# SEC_3002_HL_Power.net
KiCad netlist of a schematic drawn in Altium Designer
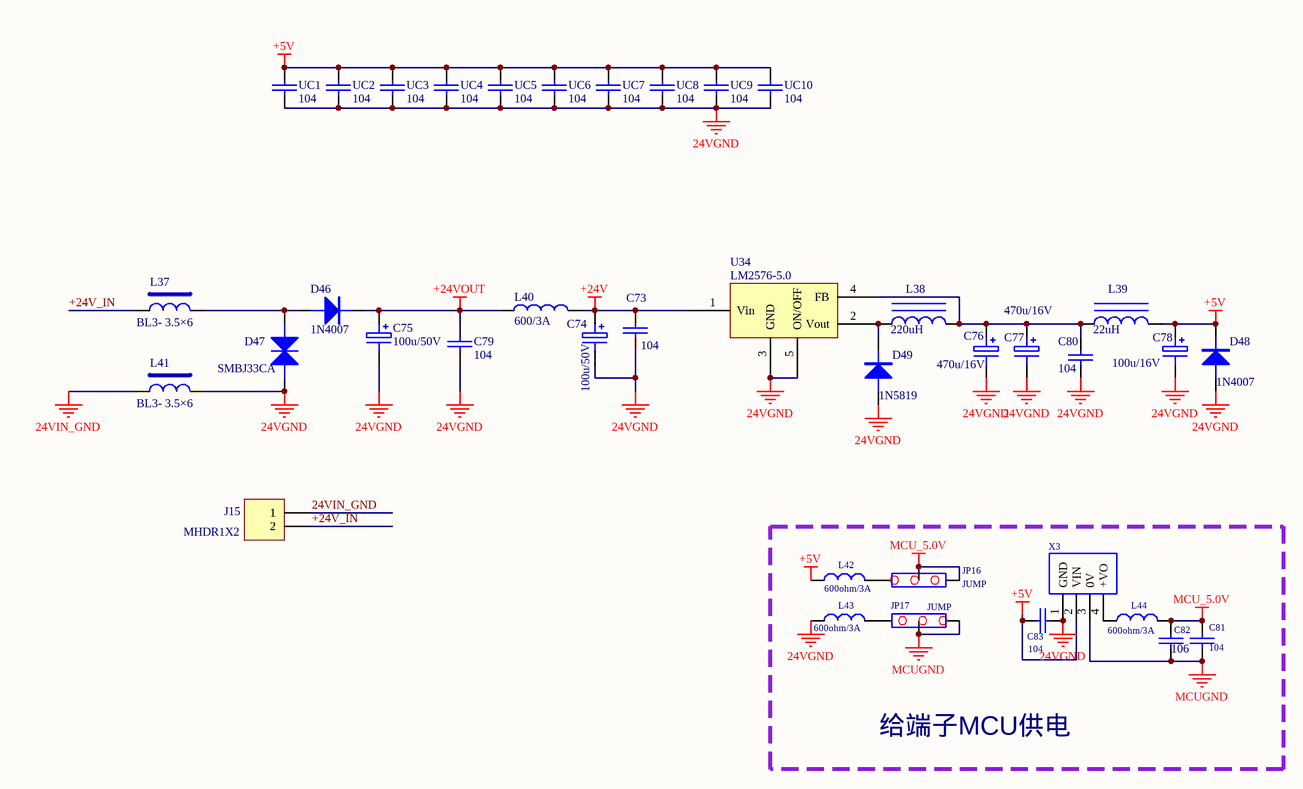
[diagram p0: SEC_3002_HL_Power.SchDoc]

(export (version "E")
  (design (tool "Eeschema 10.0.6"))
  (components
    (comp (ref "C73")
      (value "104")
      (footprint "C-0603")
      (description "Capacitor")
      (libsource (lib "*") (part "CAP"))
    )
    (comp (ref "C74")
      (value "100u/50V")
      (footprint "CAP-SMD-8*8*10")
      (description "Electrolytic Capacitor")
      (libsource (lib "*") (part "ELECTRO1"))
    )
    (comp (ref "C75")
      (value "100u/50V")
      (footprint "CAP-SMD-8*8*10")
      (description "Electrolytic Capacitor")
      (libsource (lib "*") (part "ELECTRO1"))
    )
    (comp (ref "C76")
      (value "470u/16V")
      (footprint "CAP-SMD-8*8*10")
      (description "Electrolytic Capacitor")
      (libsource (lib "*") (part "ELECTRO1"))
    )
    (comp (ref "C77")
      (value "470u/16V")
      (footprint "CAP-SMD-8*8*10")
      (description "Electrolytic Capacitor")
      (libsource (lib "*") (part "ELECTRO1"))
    )
    (comp (ref "C78")
      (value "100u/16V")
      (footprint "CAP-SMD-6.3")
      (description "Electrolytic Capacitor")
      (libsource (lib "*") (part "ELECTRO1"))
    )
    (comp (ref "C79")
      (value "104")
      (footprint "C-0603")
      (description "Capacitor")
      (libsource (lib "*") (part "CAP"))
    )
    (comp (ref "C80")
      (value "104")
      (footprint "C-0603")
      (description "Capacitor")
      (libsource (lib "*") (part "CAP"))
    )
    (comp (ref "C81")
      (value "104")
      (footprint "C-0603")
      (description "Capacitor")
      (libsource (lib "*") (part "CAP"))
    )
    (comp (ref "C82")
      (value "10V-106-±10%-[0805]")
      (footprint "C-0805")
      (description "Capacitor")
      (fields (field (name "ALTIUM_UNNAMED_1") "106"))
      (libsource (lib "*") (part "CAP"))
    )
    (comp (ref "C83")
      (value "104")
      (footprint "C-0603")
      (description "Capacitor")
      (libsource (lib "*") (part "CAP"))
    )
    (comp (ref "D46")
      (value "1N4007")
      (footprint "4526D")
      (description "Diode")
      (libsource (lib "*") (part "DIODE_A"))
    )
    (comp (ref "D47") (value "SMBJ33CA") (footprint "TVS-A") (libsource (lib "*") (part "TVS")))
    (comp (ref "D48")
      (value "1N4007")
      (footprint "4526D")
      (description "Diode")
      (libsource (lib "*") (part "DIODE_A"))
    )
    (comp (ref "D49")
      (value "1N5819")
      (footprint "4526D")
      (description "Diode")
      (libsource (lib "*") (part "DIODE_A"))
    )
    (comp (ref "J15")
      (value "MHDR1X2")
      (footprint "6.35MM-2PIN")
      (description "Header, 2-Pin")
      (fields (field (name "PUBLISHER") "Altium Limited"))
      (libsource (lib "Miscellaneous Connectors") (part "MHDR1X2"))
    )
    (comp (ref "JP16") (value "JUMP") (footprint "SIP3") (libsource (lib "*") (part "JUMP")))
    (comp (ref "JP17") (value "JUMP") (footprint "SIP3") (libsource (lib "*") (part "JUMP")))
    (comp (ref "L37")
      (value "BL3- 3.5×6")
      (footprint "L_C")
      (libsource (lib "JB-QBL-ST300_B_1") (part "INDUCTOR"))
    )
    (comp (ref "L38") (value "220uH") (footprint "L-7*7") (libsource (lib "*") (part "INDUCTOR IRON")))
    (comp (ref "L39") (value "22uH") (footprint "L-7*7") (libsource (lib "*") (part "INDUCTOR IRON")))
    (comp (ref "L40") (value "600/3A") (footprint "L-0805") (libsource (lib "*") (part "INDUCTOR1")))
    (comp (ref "L41")
      (value "BL3- 3.5×6")
      (footprint "L_C")
      (libsource (lib "JB-QBL-ST300_B_1") (part "INDUCTOR"))
    )
    (comp (ref "L42")
      (value "600ohm/3A")
      (footprint "L-0805")
      (description "60Ω-3A-[0805]")
      (fields (field (name "Comment") "BEAD"))
      (libsource (lib "*") (part "BEAD"))
    )
    (comp (ref "L43")
      (value "600ohm/3A")
      (footprint "L-0805")
      (description "60Ω-3A-[0805]")
      (fields (field (name "Comment") "BEAD"))
      (libsource (lib "*") (part "BEAD"))
    )
    (comp (ref "L44")
      (value "600ohm/3A")
      (footprint "L-0805")
      (description "60Ω-3A-[0805]")
      (fields (field (name "Comment") "BEAD"))
      (libsource (lib "*") (part "BEAD"))
    )
    (comp (ref "U34") (value "LM2576-5.0") (footprint "LM2576-5.0") (libsource (lib "*") (part "LM2576-5.0")))
    (comp (ref "UC1")
      (value "104")
      (footprint "C-0603")
      (description "Capacitor")
      (libsource (lib "*") (part "CAP"))
    )
    (comp (ref "UC2")
      (value "104")
      (footprint "C-0603")
      (description "Capacitor")
      (libsource (lib "*") (part "CAP"))
    )
    (comp (ref "UC3")
      (value "104")
      (footprint "C-0603")
      (description "Capacitor")
      (libsource (lib "*") (part "CAP"))
    )
    (comp (ref "UC4")
      (value "104")
      (footprint "C-0603")
      (description "Capacitor")
      (libsource (lib "*") (part "CAP"))
    )
    (comp (ref "UC5")
      (value "104")
      (footprint "C-0603")
      (description "Capacitor")
      (libsource (lib "*") (part "CAP"))
    )
    (comp (ref "UC6")
      (value "104")
      (footprint "C-0603")
      (description "Capacitor")
      (libsource (lib "*") (part "CAP"))
    )
    (comp (ref "UC7")
      (value "104")
      (footprint "C-0603")
      (description "Capacitor")
      (libsource (lib "*") (part "CAP"))
    )
    (comp (ref "UC8")
      (value "104")
      (footprint "C-0603")
      (description "Capacitor")
      (libsource (lib "*") (part "CAP"))
    )
    (comp (ref "UC9")
      (value "104")
      (footprint "C-0603")
      (description "Capacitor")
      (libsource (lib "*") (part "CAP"))
    )
    (comp (ref "UC10")
      (value "104")
      (footprint "C-0603")
      (description "Capacitor")
      (libsource (lib "*") (part "CAP"))
    )
    (comp (ref "X3")
      (value "B0505S-1WR2_")
      (footprint "B050S-1WR2")
      (description "B050S-1WR")
      (libsource (lib "*") (part "B0505S-1WR2_"))
    )
  )
  (nets
    (net (code "1") (name "+5V") (class "Default")
      (node (ref "C78") (pin "1") (pinfunction "1_1") (pintype "passive"))
      (node (ref "C83") (pin "1") (pinfunction "1_1") (pintype "passive"))
      (node (ref "D48") (pin "K") (pinfunction "K_K") (pintype "passive"))
      (node (ref "L39") (pin "1") (pinfunction "1_1") (pintype "passive"))
      (node (ref "L42") (pin "1") (pintype "passive"))
      (node (ref "UC1") (pin "1") (pinfunction "1_1") (pintype "passive"))
      (node (ref "UC10") (pin "1") (pinfunction "1_1") (pintype "passive"))
      (node (ref "UC2") (pin "1") (pinfunction "1_1") (pintype "passive"))
      (node (ref "UC3") (pin "1") (pinfunction "1_1") (pintype "passive"))
      (node (ref "UC4") (pin "1") (pinfunction "1_1") (pintype "passive"))
      (node (ref "UC5") (pin "1") (pinfunction "1_1") (pintype "passive"))
      (node (ref "UC6") (pin "1") (pinfunction "1_1") (pintype "passive"))
      (node (ref "UC7") (pin "1") (pinfunction "1_1") (pintype "passive"))
      (node (ref "UC8") (pin "1") (pinfunction "1_1") (pintype "passive"))
      (node (ref "UC9") (pin "1") (pinfunction "1_1") (pintype "passive"))
      (node (ref "X3") (pin "2") (pinfunction "VIN_2") (pintype "passive"))
    )
    (net (code "2") (name "+24V") (class "Default")
      (node (ref "C73") (pin "1") (pinfunction "1_1") (pintype "passive"))
      (node (ref "C74") (pin "1") (pinfunction "1_1") (pintype "passive"))
      (node (ref "L40") (pin "2") (pinfunction "2_2") (pintype "passive"))
      (node (ref "U34") (pin "1") (pinfunction "Vin_1") (pintype "passive"))
    )
    (net (code "3") (name "+24VOUT") (class "Default")
      (node (ref "C75") (pin "1") (pinfunction "1_1") (pintype "passive"))
      (node (ref "C79") (pin "1") (pinfunction "1_1") (pintype "passive"))
      (node (ref "D46") (pin "K") (pinfunction "K_K") (pintype "passive"))
      (node (ref "L40") (pin "1") (pinfunction "1_1") (pintype "passive"))
    )
    (net (code "4") (name "/+24V_IN") (class "Default")
      (node (ref "J15") (pin "2") (pinfunction "2_2") (pintype "passive"))
      (node (ref "L37") (pin "1") (pinfunction "1_1") (pintype "passive"))
    )
    (net (code "5") (name "24VGND") (class "Default")
      (node (ref "C73") (pin "2") (pinfunction "2_2") (pintype "passive"))
      (node (ref "C74") (pin "2") (pinfunction "2_2") (pintype "passive"))
      (node (ref "C75") (pin "2") (pinfunction "2_2") (pintype "passive"))
      (node (ref "C76") (pin "2") (pinfunction "2_2") (pintype "passive"))
      (node (ref "C77") (pin "2") (pinfunction "2_2") (pintype "passive"))
      (node (ref "C78") (pin "2") (pinfunction "2_2") (pintype "passive"))
      (node (ref "C79") (pin "2") (pinfunction "2_2") (pintype "passive"))
      (node (ref "C80") (pin "2") (pinfunction "2_2") (pintype "passive"))
      (node (ref "C83") (pin "2") (pinfunction "2_2") (pintype "passive"))
      (node (ref "D47") (pin "A") (pinfunction "A_A") (pintype "passive"))
      (node (ref "D48") (pin "A") (pinfunction "A_A") (pintype "passive"))
      (node (ref "D49") (pin "A") (pinfunction "A_A") (pintype "passive"))
      (node (ref "L41") (pin "2") (pinfunction "2_2") (pintype "passive"))
      (node (ref "L43") (pin "1") (pintype "passive"))
      (node (ref "U34") (pin "3") (pinfunction "GND_3") (pintype "passive"))
      (node (ref "U34") (pin "5") (pinfunction "ON/OFF_5") (pintype "passive"))
      (node (ref "UC1") (pin "2") (pinfunction "2_2") (pintype "passive"))
      (node (ref "UC10") (pin "2") (pinfunction "2_2") (pintype "passive"))
      (node (ref "UC2") (pin "2") (pinfunction "2_2") (pintype "passive"))
      (node (ref "UC3") (pin "2") (pinfunction "2_2") (pintype "passive"))
      (node (ref "UC4") (pin "2") (pinfunction "2_2") (pintype "passive"))
      (node (ref "UC5") (pin "2") (pinfunction "2_2") (pintype "passive"))
      (node (ref "UC6") (pin "2") (pinfunction "2_2") (pintype "passive"))
      (node (ref "UC7") (pin "2") (pinfunction "2_2") (pintype "passive"))
      (node (ref "UC8") (pin "2") (pinfunction "2_2") (pintype "passive"))
      (node (ref "UC9") (pin "2") (pinfunction "2_2") (pintype "passive"))
      (node (ref "X3") (pin "1") (pinfunction "GND_1") (pintype "passive"))
    )
    (net (code "6") (name "24VIN_GND") (class "Default")
      (node (ref "J15") (pin "1") (pinfunction "1_1") (pintype "passive"))
      (node (ref "L41") (pin "1") (pinfunction "1_1") (pintype "passive"))
    )
    (net (code "7") (name "MCUGND") (class "Default")
      (node (ref "C81") (pin "2") (pinfunction "2_2") (pintype "passive"))
      (node (ref "C82") (pin "2") (pinfunction "2_2") (pintype "passive"))
      (node (ref "JP17") (pin "2") (pinfunction "2_2") (pintype "passive"))
      (node (ref "JP17") (pin "3") (pinfunction "3_3") (pintype "passive"))
      (node (ref "X3") (pin "3") (pinfunction "0V_3") (pintype "passive"))
    )
    (net (code "8") (name "MCU_5.0V") (class "Default")
      (node (ref "C81") (pin "1") (pinfunction "1_1") (pintype "passive"))
      (node (ref "C82") (pin "1") (pinfunction "1_1") (pintype "passive"))
      (node (ref "JP16") (pin "1") (pinfunction "1_1") (pintype "passive"))
      (node (ref "JP16") (pin "2") (pinfunction "2_2") (pintype "passive"))
      (node (ref "L44") (pin "2") (pintype "passive"))
    )
    (net (code "9") (name "Net-(D46-PadA)") (class "Default")
      (node (ref "D46") (pin "A") (pinfunction "A_A") (pintype "passive"))
      (node (ref "D47") (pin "K") (pinfunction "K_K") (pintype "passive"))
      (node (ref "L37") (pin "2") (pinfunction "2_2") (pintype "passive"))
    )
    (net (code "10") (name "Net-(JP16-Pad3)") (class "Default")
      (node (ref "JP16") (pin "3") (pinfunction "3_3") (pintype "passive"))
      (node (ref "L42") (pin "2") (pintype "passive"))
    )
    (net (code "11") (name "Net-(JP17-Pad1)") (class "Default")
      (node (ref "JP17") (pin "1") (pinfunction "1_1") (pintype "passive"))
      (node (ref "L43") (pin "2") (pintype "passive"))
    )
    (net (code "12") (name "Net-(U34-FB)") (class "Default")
      (node (ref "C76") (pin "1") (pinfunction "1_1") (pintype "passive"))
      (node (ref "C77") (pin "1") (pinfunction "1_1") (pintype "passive"))
      (node (ref "C80") (pin "1") (pinfunction "1_1") (pintype "passive"))
      (node (ref "L38") (pin "1") (pinfunction "1_1") (pintype "passive"))
      (node (ref "L39") (pin "2") (pinfunction "2_2") (pintype "passive"))
      (node (ref "U34") (pin "4") (pinfunction "FB_4") (pintype "passive"))
    )
    (net (code "13") (name "Net-(U34-Vout)") (class "Default")
      (node (ref "D49") (pin "K") (pinfunction "K_K") (pintype "passive"))
      (node (ref "L38") (pin "2") (pinfunction "2_2") (pintype "passive"))
      (node (ref "U34") (pin "2") (pinfunction "Vout_2") (pintype "passive"))
    )
    (net (code "14") (name "Net-(X3-+VO)") (class "Default")
      (node (ref "L44") (pin "1") (pintype "passive"))
      (node (ref "X3") (pin "4") (pinfunction "+VO_4") (pintype "passive"))
    )
  )
)
